# arrayboard_r0.net
KiCad netlist of a schematic drawn in EAGLE
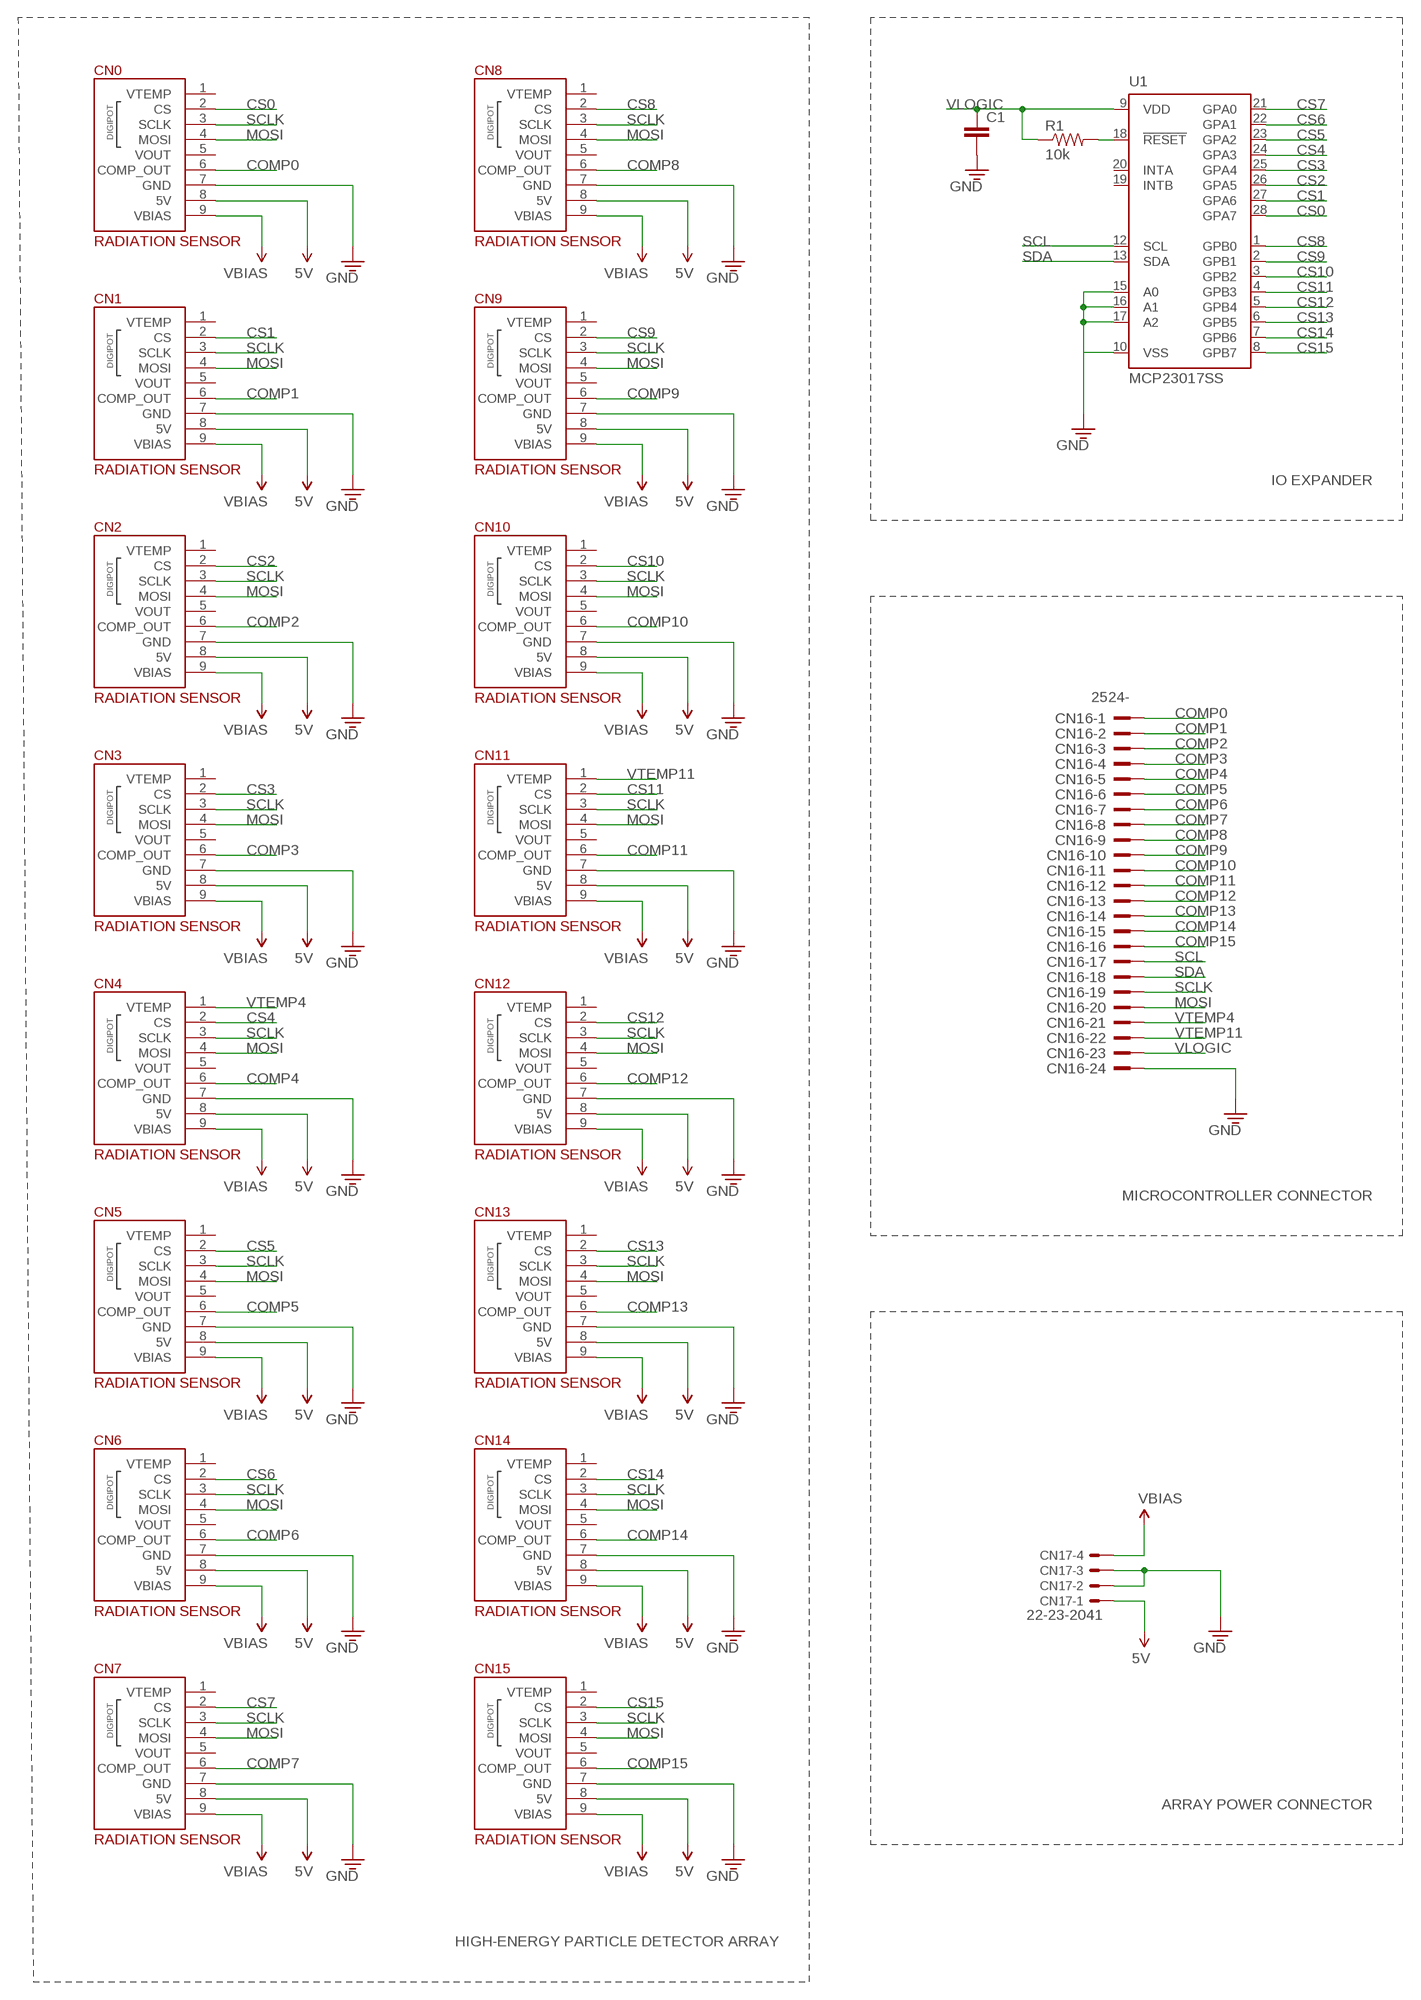
[diagram p0: schematic, sheet 1]

(export (version "E")
  (design (tool "Eeschema 10.0.6"))
  (components
    (comp (ref "C1")
      (value "CAP0603")
      (footprint "eagle-import:0603")
      (libsource (lib "eagle-import") (part "CAP0603"))
    )
    (comp (ref "CN0")
      (value "RADIATION-SENSOR-REV1")
      (footprint "eagle-import:RADIATION-SENSOR-REV1")
      (libsource (lib "eagle-import") (part "RADIATION-SENSOR-REV1"))
    )
    (comp (ref "CN1")
      (value "RADIATION-SENSOR-REV1")
      (footprint "eagle-import:RADIATION-SENSOR-REV1")
      (libsource (lib "eagle-import") (part "RADIATION-SENSOR-REV1"))
    )
    (comp (ref "CN2")
      (value "RADIATION-SENSOR-REV1")
      (footprint "eagle-import:RADIATION-SENSOR-REV1")
      (libsource (lib "eagle-import") (part "RADIATION-SENSOR-REV1"))
    )
    (comp (ref "CN3")
      (value "RADIATION-SENSOR-REV1")
      (footprint "eagle-import:RADIATION-SENSOR-REV1")
      (libsource (lib "eagle-import") (part "RADIATION-SENSOR-REV1"))
    )
    (comp (ref "CN4")
      (value "RADIATION-SENSOR-REV1")
      (footprint "eagle-import:RADIATION-SENSOR-REV1")
      (libsource (lib "eagle-import") (part "RADIATION-SENSOR-REV1"))
    )
    (comp (ref "CN5")
      (value "RADIATION-SENSOR-REV1")
      (footprint "eagle-import:RADIATION-SENSOR-REV1")
      (libsource (lib "eagle-import") (part "RADIATION-SENSOR-REV1"))
    )
    (comp (ref "CN6")
      (value "RADIATION-SENSOR-REV1")
      (footprint "eagle-import:RADIATION-SENSOR-REV1")
      (libsource (lib "eagle-import") (part "RADIATION-SENSOR-REV1"))
    )
    (comp (ref "CN7")
      (value "RADIATION-SENSOR-REV1")
      (footprint "eagle-import:RADIATION-SENSOR-REV1")
      (libsource (lib "eagle-import") (part "RADIATION-SENSOR-REV1"))
    )
    (comp (ref "CN8")
      (value "RADIATION-SENSOR-REV1")
      (footprint "eagle-import:RADIATION-SENSOR-REV1")
      (libsource (lib "eagle-import") (part "RADIATION-SENSOR-REV1"))
    )
    (comp (ref "CN9")
      (value "RADIATION-SENSOR-REV1")
      (footprint "eagle-import:RADIATION-SENSOR-REV1")
      (libsource (lib "eagle-import") (part "RADIATION-SENSOR-REV1"))
    )
    (comp (ref "CN10")
      (value "RADIATION-SENSOR-REV1")
      (footprint "eagle-import:RADIATION-SENSOR-REV1")
      (libsource (lib "eagle-import") (part "RADIATION-SENSOR-REV1"))
    )
    (comp (ref "CN11")
      (value "RADIATION-SENSOR-REV1")
      (footprint "eagle-import:RADIATION-SENSOR-REV1")
      (libsource (lib "eagle-import") (part "RADIATION-SENSOR-REV1"))
    )
    (comp (ref "CN12")
      (value "RADIATION-SENSOR-REV1")
      (footprint "eagle-import:RADIATION-SENSOR-REV1")
      (libsource (lib "eagle-import") (part "RADIATION-SENSOR-REV1"))
    )
    (comp (ref "CN13")
      (value "RADIATION-SENSOR-REV1")
      (footprint "eagle-import:RADIATION-SENSOR-REV1")
      (libsource (lib "eagle-import") (part "RADIATION-SENSOR-REV1"))
    )
    (comp (ref "CN14")
      (value "RADIATION-SENSOR-REV1")
      (footprint "eagle-import:RADIATION-SENSOR-REV1")
      (libsource (lib "eagle-import") (part "RADIATION-SENSOR-REV1"))
    )
    (comp (ref "CN15")
      (value "RADIATION-SENSOR-REV1")
      (footprint "eagle-import:RADIATION-SENSOR-REV1")
      (libsource (lib "eagle-import") (part "RADIATION-SENSOR-REV1"))
    )
    (comp (ref "CN16")
      (value "2524-")
      (footprint "eagle-import:PAK100_2500-24")
      (libsource (lib "eagle-import") (part "2524-"))
    )
    (comp (ref "CN17")
      (value "22-23-2041")
      (footprint "eagle-import:22-23-2041")
      (fields (field (name "MF") "MOLEX"))
      (libsource (lib "eagle-import") (part "22-23-2041"))
    )
    (comp (ref "R1")
      (value "10k")
      (footprint "eagle-import:0603")
      (libsource (lib "eagle-import") (part "RESISTOR0603"))
    )
    (comp (ref "U1")
      (value "MCP23017SS")
      (footprint "eagle-import:SSOP28")
      (libsource (lib "eagle-import") (part "MCP23017SS"))
    )
  )
  (nets
    (net (code "1") (name "/COMP0") (class "Default")
      (node (ref "CN0") (pin "6") (pinfunction "COMP_OUT_6") (pintype "bidirectional"))
      (node (ref "CN16") (pin "1") (pinfunction "KL_1") (pintype "passive"))
    )
    (net (code "2") (name "/COMP1") (class "Default")
      (node (ref "CN1") (pin "6") (pinfunction "COMP_OUT_6") (pintype "bidirectional"))
      (node (ref "CN16") (pin "2") (pinfunction "KL_2") (pintype "passive"))
    )
    (net (code "3") (name "/COMP2") (class "Default")
      (node (ref "CN16") (pin "3") (pinfunction "KL_3") (pintype "passive"))
      (node (ref "CN2") (pin "6") (pinfunction "COMP_OUT_6") (pintype "bidirectional"))
    )
    (net (code "4") (name "/COMP3") (class "Default")
      (node (ref "CN16") (pin "4") (pinfunction "KL_4") (pintype "passive"))
      (node (ref "CN3") (pin "6") (pinfunction "COMP_OUT_6") (pintype "bidirectional"))
    )
    (net (code "5") (name "/COMP4") (class "Default")
      (node (ref "CN16") (pin "5") (pinfunction "KL_5") (pintype "passive"))
      (node (ref "CN4") (pin "6") (pinfunction "COMP_OUT_6") (pintype "bidirectional"))
    )
    (net (code "6") (name "/COMP5") (class "Default")
      (node (ref "CN16") (pin "6") (pinfunction "KL_6") (pintype "passive"))
      (node (ref "CN5") (pin "6") (pinfunction "COMP_OUT_6") (pintype "bidirectional"))
    )
    (net (code "7") (name "/COMP6") (class "Default")
      (node (ref "CN16") (pin "7") (pinfunction "KL_7") (pintype "passive"))
      (node (ref "CN6") (pin "6") (pinfunction "COMP_OUT_6") (pintype "bidirectional"))
    )
    (net (code "8") (name "/COMP7") (class "Default")
      (node (ref "CN16") (pin "8") (pinfunction "KL_8") (pintype "passive"))
      (node (ref "CN7") (pin "6") (pinfunction "COMP_OUT_6") (pintype "bidirectional"))
    )
    (net (code "9") (name "/COMP8") (class "Default")
      (node (ref "CN16") (pin "9") (pinfunction "KL_9") (pintype "passive"))
      (node (ref "CN8") (pin "6") (pinfunction "COMP_OUT_6") (pintype "bidirectional"))
    )
    (net (code "10") (name "/COMP9") (class "Default")
      (node (ref "CN16") (pin "10") (pinfunction "KL_10") (pintype "passive"))
      (node (ref "CN9") (pin "6") (pinfunction "COMP_OUT_6") (pintype "bidirectional"))
    )
    (net (code "11") (name "/COMP10") (class "Default")
      (node (ref "CN10") (pin "6") (pinfunction "COMP_OUT_6") (pintype "bidirectional"))
      (node (ref "CN16") (pin "11") (pinfunction "KL_11") (pintype "passive"))
    )
    (net (code "12") (name "/COMP11") (class "Default")
      (node (ref "CN11") (pin "6") (pinfunction "COMP_OUT_6") (pintype "bidirectional"))
      (node (ref "CN16") (pin "12") (pinfunction "KL_12") (pintype "passive"))
    )
    (net (code "13") (name "/COMP12") (class "Default")
      (node (ref "CN12") (pin "6") (pinfunction "COMP_OUT_6") (pintype "bidirectional"))
      (node (ref "CN16") (pin "13") (pinfunction "KL_13") (pintype "passive"))
    )
    (net (code "14") (name "/COMP13") (class "Default")
      (node (ref "CN13") (pin "6") (pinfunction "COMP_OUT_6") (pintype "bidirectional"))
      (node (ref "CN16") (pin "14") (pinfunction "KL_14") (pintype "passive"))
    )
    (net (code "15") (name "/COMP14") (class "Default")
      (node (ref "CN14") (pin "6") (pinfunction "COMP_OUT_6") (pintype "bidirectional"))
      (node (ref "CN16") (pin "15") (pinfunction "KL_15") (pintype "passive"))
    )
    (net (code "16") (name "/COMP15") (class "Default")
      (node (ref "CN15") (pin "6") (pinfunction "COMP_OUT_6") (pintype "bidirectional"))
      (node (ref "CN16") (pin "16") (pinfunction "KL_16") (pintype "passive"))
    )
    (net (code "17") (name "/CS0") (class "Default")
      (node (ref "CN0") (pin "2") (pinfunction "CS_2") (pintype "bidirectional"))
      (node (ref "U1") (pin "28") (pinfunction "GPA7_28") (pintype "bidirectional"))
    )
    (net (code "18") (name "/CS1") (class "Default")
      (node (ref "CN1") (pin "2") (pinfunction "CS_2") (pintype "bidirectional"))
      (node (ref "U1") (pin "27") (pinfunction "GPA6_27") (pintype "bidirectional"))
    )
    (net (code "19") (name "/CS2") (class "Default")
      (node (ref "CN2") (pin "2") (pinfunction "CS_2") (pintype "bidirectional"))
      (node (ref "U1") (pin "26") (pinfunction "GPA5_26") (pintype "bidirectional"))
    )
    (net (code "20") (name "/CS3") (class "Default")
      (node (ref "CN3") (pin "2") (pinfunction "CS_2") (pintype "bidirectional"))
      (node (ref "U1") (pin "25") (pinfunction "GPA4_25") (pintype "bidirectional"))
    )
    (net (code "21") (name "/CS4") (class "Default")
      (node (ref "CN4") (pin "2") (pinfunction "CS_2") (pintype "bidirectional"))
      (node (ref "U1") (pin "24") (pinfunction "GPA3_24") (pintype "bidirectional"))
    )
    (net (code "22") (name "/CS5") (class "Default")
      (node (ref "CN5") (pin "2") (pinfunction "CS_2") (pintype "bidirectional"))
      (node (ref "U1") (pin "23") (pinfunction "GPA2_23") (pintype "bidirectional"))
    )
    (net (code "23") (name "/CS6") (class "Default")
      (node (ref "CN6") (pin "2") (pinfunction "CS_2") (pintype "bidirectional"))
      (node (ref "U1") (pin "22") (pinfunction "GPA1_22") (pintype "bidirectional"))
    )
    (net (code "24") (name "/CS7") (class "Default")
      (node (ref "CN7") (pin "2") (pinfunction "CS_2") (pintype "bidirectional"))
      (node (ref "U1") (pin "21") (pinfunction "GPA0_21") (pintype "bidirectional"))
    )
    (net (code "25") (name "/CS8") (class "Default")
      (node (ref "CN8") (pin "2") (pinfunction "CS_2") (pintype "bidirectional"))
      (node (ref "U1") (pin "1") (pinfunction "GPB0_1") (pintype "bidirectional"))
    )
    (net (code "26") (name "/CS9") (class "Default")
      (node (ref "CN9") (pin "2") (pinfunction "CS_2") (pintype "bidirectional"))
      (node (ref "U1") (pin "2") (pinfunction "GPB1_2") (pintype "bidirectional"))
    )
    (net (code "27") (name "/CS10") (class "Default")
      (node (ref "CN10") (pin "2") (pinfunction "CS_2") (pintype "bidirectional"))
      (node (ref "U1") (pin "3") (pinfunction "GPB2_3") (pintype "bidirectional"))
    )
    (net (code "28") (name "/CS11") (class "Default")
      (node (ref "CN11") (pin "2") (pinfunction "CS_2") (pintype "bidirectional"))
      (node (ref "U1") (pin "4") (pinfunction "GPB3_4") (pintype "bidirectional"))
    )
    (net (code "29") (name "/CS12") (class "Default")
      (node (ref "CN12") (pin "2") (pinfunction "CS_2") (pintype "bidirectional"))
      (node (ref "U1") (pin "5") (pinfunction "GPB4_5") (pintype "bidirectional"))
    )
    (net (code "30") (name "/CS13") (class "Default")
      (node (ref "CN13") (pin "2") (pinfunction "CS_2") (pintype "bidirectional"))
      (node (ref "U1") (pin "6") (pinfunction "GPB5_6") (pintype "bidirectional"))
    )
    (net (code "31") (name "/CS14") (class "Default")
      (node (ref "CN14") (pin "2") (pinfunction "CS_2") (pintype "bidirectional"))
      (node (ref "U1") (pin "7") (pinfunction "GPB6_7") (pintype "bidirectional"))
    )
    (net (code "32") (name "/CS15") (class "Default")
      (node (ref "CN15") (pin "2") (pinfunction "CS_2") (pintype "bidirectional"))
      (node (ref "U1") (pin "8") (pinfunction "GPB7_8") (pintype "bidirectional"))
    )
    (net (code "33") (name "/MOSI") (class "Default")
      (node (ref "CN0") (pin "4") (pinfunction "MOSI_4") (pintype "bidirectional"))
      (node (ref "CN1") (pin "4") (pinfunction "MOSI_4") (pintype "bidirectional"))
      (node (ref "CN10") (pin "4") (pinfunction "MOSI_4") (pintype "bidirectional"))
      (node (ref "CN11") (pin "4") (pinfunction "MOSI_4") (pintype "bidirectional"))
      (node (ref "CN12") (pin "4") (pinfunction "MOSI_4") (pintype "bidirectional"))
      (node (ref "CN13") (pin "4") (pinfunction "MOSI_4") (pintype "bidirectional"))
      (node (ref "CN14") (pin "4") (pinfunction "MOSI_4") (pintype "bidirectional"))
      (node (ref "CN15") (pin "4") (pinfunction "MOSI_4") (pintype "bidirectional"))
      (node (ref "CN16") (pin "20") (pinfunction "KL_20") (pintype "passive"))
      (node (ref "CN2") (pin "4") (pinfunction "MOSI_4") (pintype "bidirectional"))
      (node (ref "CN3") (pin "4") (pinfunction "MOSI_4") (pintype "bidirectional"))
      (node (ref "CN4") (pin "4") (pinfunction "MOSI_4") (pintype "bidirectional"))
      (node (ref "CN5") (pin "4") (pinfunction "MOSI_4") (pintype "bidirectional"))
      (node (ref "CN6") (pin "4") (pinfunction "MOSI_4") (pintype "bidirectional"))
      (node (ref "CN7") (pin "4") (pinfunction "MOSI_4") (pintype "bidirectional"))
      (node (ref "CN8") (pin "4") (pinfunction "MOSI_4") (pintype "bidirectional"))
      (node (ref "CN9") (pin "4") (pinfunction "MOSI_4") (pintype "bidirectional"))
    )
    (net (code "34") (name "/SCL") (class "Default")
      (node (ref "CN16") (pin "17") (pinfunction "KL_17") (pintype "passive"))
      (node (ref "U1") (pin "12") (pinfunction "SCL_12") (pintype "input"))
    )
    (net (code "35") (name "/SCLK") (class "Default")
      (node (ref "CN0") (pin "3") (pinfunction "SCLK_3") (pintype "bidirectional"))
      (node (ref "CN1") (pin "3") (pinfunction "SCLK_3") (pintype "bidirectional"))
      (node (ref "CN10") (pin "3") (pinfunction "SCLK_3") (pintype "bidirectional"))
      (node (ref "CN11") (pin "3") (pinfunction "SCLK_3") (pintype "bidirectional"))
      (node (ref "CN12") (pin "3") (pinfunction "SCLK_3") (pintype "bidirectional"))
      (node (ref "CN13") (pin "3") (pinfunction "SCLK_3") (pintype "bidirectional"))
      (node (ref "CN14") (pin "3") (pinfunction "SCLK_3") (pintype "bidirectional"))
      (node (ref "CN15") (pin "3") (pinfunction "SCLK_3") (pintype "bidirectional"))
      (node (ref "CN16") (pin "19") (pinfunction "KL_19") (pintype "passive"))
      (node (ref "CN2") (pin "3") (pinfunction "SCLK_3") (pintype "bidirectional"))
      (node (ref "CN3") (pin "3") (pinfunction "SCLK_3") (pintype "bidirectional"))
      (node (ref "CN4") (pin "3") (pinfunction "SCLK_3") (pintype "bidirectional"))
      (node (ref "CN5") (pin "3") (pinfunction "SCLK_3") (pintype "bidirectional"))
      (node (ref "CN6") (pin "3") (pinfunction "SCLK_3") (pintype "bidirectional"))
      (node (ref "CN7") (pin "3") (pinfunction "SCLK_3") (pintype "bidirectional"))
      (node (ref "CN8") (pin "3") (pinfunction "SCLK_3") (pintype "bidirectional"))
      (node (ref "CN9") (pin "3") (pinfunction "SCLK_3") (pintype "bidirectional"))
    )
    (net (code "36") (name "/SDA") (class "Default")
      (node (ref "CN16") (pin "18") (pinfunction "KL_18") (pintype "passive"))
      (node (ref "U1") (pin "13") (pinfunction "SDA_13") (pintype "bidirectional"))
    )
    (net (code "37") (name "/VLOGIC") (class "Default")
      (node (ref "C1") (pin "1") (pinfunction "1_1") (pintype "passive"))
      (node (ref "CN16") (pin "23") (pinfunction "KL_23") (pintype "passive"))
      (node (ref "R1") (pin "1") (pinfunction "1_1") (pintype "passive"))
      (node (ref "U1") (pin "9") (pinfunction "VDD_9") (pintype "power_in"))
    )
    (net (code "38") (name "/VTEMP4") (class "Default")
      (node (ref "CN16") (pin "21") (pinfunction "KL_21") (pintype "passive"))
      (node (ref "CN4") (pin "1") (pinfunction "VTEMP_1") (pintype "bidirectional"))
    )
    (net (code "39") (name "/VTEMP11") (class "Default")
      (node (ref "CN11") (pin "1") (pinfunction "VTEMP_1") (pintype "bidirectional"))
      (node (ref "CN16") (pin "22") (pinfunction "KL_22") (pintype "passive"))
    )
    (net (code "40") (name "5V") (class "Default")
      (node (ref "CN0") (pin "8") (pinfunction "5V_8") (pintype "bidirectional"))
      (node (ref "CN1") (pin "8") (pinfunction "5V_8") (pintype "bidirectional"))
      (node (ref "CN10") (pin "8") (pinfunction "5V_8") (pintype "bidirectional"))
      (node (ref "CN11") (pin "8") (pinfunction "5V_8") (pintype "bidirectional"))
      (node (ref "CN12") (pin "8") (pinfunction "5V_8") (pintype "bidirectional"))
      (node (ref "CN13") (pin "8") (pinfunction "5V_8") (pintype "bidirectional"))
      (node (ref "CN14") (pin "8") (pinfunction "5V_8") (pintype "bidirectional"))
      (node (ref "CN15") (pin "8") (pinfunction "5V_8") (pintype "bidirectional"))
      (node (ref "CN17") (pin "1") (pinfunction "S_1") (pintype "passive"))
      (node (ref "CN2") (pin "8") (pinfunction "5V_8") (pintype "bidirectional"))
      (node (ref "CN3") (pin "8") (pinfunction "5V_8") (pintype "bidirectional"))
      (node (ref "CN4") (pin "8") (pinfunction "5V_8") (pintype "bidirectional"))
      (node (ref "CN5") (pin "8") (pinfunction "5V_8") (pintype "bidirectional"))
      (node (ref "CN6") (pin "8") (pinfunction "5V_8") (pintype "bidirectional"))
      (node (ref "CN7") (pin "8") (pinfunction "5V_8") (pintype "bidirectional"))
      (node (ref "CN8") (pin "8") (pinfunction "5V_8") (pintype "bidirectional"))
      (node (ref "CN9") (pin "8") (pinfunction "5V_8") (pintype "bidirectional"))
    )
    (net (code "41") (name "GND") (class "Default")
      (node (ref "C1") (pin "2") (pinfunction "2_2") (pintype "passive"))
      (node (ref "CN0") (pin "7") (pinfunction "GND_7") (pintype "bidirectional"))
      (node (ref "CN1") (pin "7") (pinfunction "GND_7") (pintype "bidirectional"))
      (node (ref "CN10") (pin "7") (pinfunction "GND_7") (pintype "bidirectional"))
      (node (ref "CN11") (pin "7") (pinfunction "GND_7") (pintype "bidirectional"))
      (node (ref "CN12") (pin "7") (pinfunction "GND_7") (pintype "bidirectional"))
      (node (ref "CN13") (pin "7") (pinfunction "GND_7") (pintype "bidirectional"))
      (node (ref "CN14") (pin "7") (pinfunction "GND_7") (pintype "bidirectional"))
      (node (ref "CN15") (pin "7") (pinfunction "GND_7") (pintype "bidirectional"))
      (node (ref "CN16") (pin "24") (pinfunction "KL_24") (pintype "passive"))
      (node (ref "CN17") (pin "2") (pinfunction "S_2") (pintype "passive"))
      (node (ref "CN17") (pin "3") (pinfunction "S_3") (pintype "passive"))
      (node (ref "CN2") (pin "7") (pinfunction "GND_7") (pintype "bidirectional"))
      (node (ref "CN3") (pin "7") (pinfunction "GND_7") (pintype "bidirectional"))
      (node (ref "CN4") (pin "7") (pinfunction "GND_7") (pintype "bidirectional"))
      (node (ref "CN5") (pin "7") (pinfunction "GND_7") (pintype "bidirectional"))
      (node (ref "CN6") (pin "7") (pinfunction "GND_7") (pintype "bidirectional"))
      (node (ref "CN7") (pin "7") (pinfunction "GND_7") (pintype "bidirectional"))
      (node (ref "CN8") (pin "7") (pinfunction "GND_7") (pintype "bidirectional"))
      (node (ref "CN9") (pin "7") (pinfunction "GND_7") (pintype "bidirectional"))
      (node (ref "U1") (pin "10") (pinfunction "VSS_10") (pintype "power_in"))
      (node (ref "U1") (pin "15") (pinfunction "A0_15") (pintype "input"))
      (node (ref "U1") (pin "16") (pinfunction "A1_16") (pintype "input"))
      (node (ref "U1") (pin "17") (pinfunction "A2_17") (pintype "input"))
    )
    (net (code "42") (name "Net-(U1-~{RESET})") (class "Default")
      (node (ref "R1") (pin "2") (pinfunction "2_2") (pintype "passive"))
      (node (ref "U1") (pin "18") (pinfunction "~{RESET}_18") (pintype "input"))
    )
    (net (code "43") (name "VBIAS") (class "Default")
      (node (ref "CN0") (pin "9") (pinfunction "VBIAS_9") (pintype "bidirectional"))
      (node (ref "CN1") (pin "9") (pinfunction "VBIAS_9") (pintype "bidirectional"))
      (node (ref "CN10") (pin "9") (pinfunction "VBIAS_9") (pintype "bidirectional"))
      (node (ref "CN11") (pin "9") (pinfunction "VBIAS_9") (pintype "bidirectional"))
      (node (ref "CN12") (pin "9") (pinfunction "VBIAS_9") (pintype "bidirectional"))
      (node (ref "CN13") (pin "9") (pinfunction "VBIAS_9") (pintype "bidirectional"))
      (node (ref "CN14") (pin "9") (pinfunction "VBIAS_9") (pintype "bidirectional"))
      (node (ref "CN15") (pin "9") (pinfunction "VBIAS_9") (pintype "bidirectional"))
      (node (ref "CN17") (pin "4") (pinfunction "S_4") (pintype "passive"))
      (node (ref "CN2") (pin "9") (pinfunction "VBIAS_9") (pintype "bidirectional"))
      (node (ref "CN3") (pin "9") (pinfunction "VBIAS_9") (pintype "bidirectional"))
      (node (ref "CN4") (pin "9") (pinfunction "VBIAS_9") (pintype "bidirectional"))
      (node (ref "CN5") (pin "9") (pinfunction "VBIAS_9") (pintype "bidirectional"))
      (node (ref "CN6") (pin "9") (pinfunction "VBIAS_9") (pintype "bidirectional"))
      (node (ref "CN7") (pin "9") (pinfunction "VBIAS_9") (pintype "bidirectional"))
      (node (ref "CN8") (pin "9") (pinfunction "VBIAS_9") (pintype "bidirectional"))
      (node (ref "CN9") (pin "9") (pinfunction "VBIAS_9") (pintype "bidirectional"))
    )
    (net (code "44") (name "unconnected-(CN0-VOUT-Pad5)") (class "Default")
      (node (ref "CN0") (pin "5") (pinfunction "VOUT_5") (pintype "bidirectional"))
    )
    (net (code "45") (name "unconnected-(CN0-VTEMP-Pad1)") (class "Default")
      (node (ref "CN0") (pin "1") (pinfunction "VTEMP_1") (pintype "bidirectional"))
    )
    (net (code "46") (name "unconnected-(CN1-VOUT-Pad5)") (class "Default")
      (node (ref "CN1") (pin "5") (pinfunction "VOUT_5") (pintype "bidirectional"))
    )
    (net (code "47") (name "unconnected-(CN1-VTEMP-Pad1)") (class "Default")
      (node (ref "CN1") (pin "1") (pinfunction "VTEMP_1") (pintype "bidirectional"))
    )
    (net (code "48") (name "unconnected-(CN2-VOUT-Pad5)") (class "Default")
      (node (ref "CN2") (pin "5") (pinfunction "VOUT_5") (pintype "bidirectional"))
    )
    (net (code "49") (name "unconnected-(CN2-VTEMP-Pad1)") (class "Default")
      (node (ref "CN2") (pin "1") (pinfunction "VTEMP_1") (pintype "bidirectional"))
    )
    (net (code "50") (name "unconnected-(CN3-VOUT-Pad5)") (class "Default")
      (node (ref "CN3") (pin "5") (pinfunction "VOUT_5") (pintype "bidirectional"))
    )
    (net (code "51") (name "unconnected-(CN3-VTEMP-Pad1)") (class "Default")
      (node (ref "CN3") (pin "1") (pinfunction "VTEMP_1") (pintype "bidirectional"))
    )
    (net (code "52") (name "unconnected-(CN4-VOUT-Pad5)") (class "Default")
      (node (ref "CN4") (pin "5") (pinfunction "VOUT_5") (pintype "bidirectional"))
    )
    (net (code "53") (name "unconnected-(CN5-VOUT-Pad5)") (class "Default")
      (node (ref "CN5") (pin "5") (pinfunction "VOUT_5") (pintype "bidirectional"))
    )
    (net (code "54") (name "unconnected-(CN5-VTEMP-Pad1)") (class "Default")
      (node (ref "CN5") (pin "1") (pinfunction "VTEMP_1") (pintype "bidirectional"))
    )
    (net (code "55") (name "unconnected-(CN6-VOUT-Pad5)") (class "Default")
      (node (ref "CN6") (pin "5") (pinfunction "VOUT_5") (pintype "bidirectional"))
    )
    (net (code "56") (name "unconnected-(CN6-VTEMP-Pad1)") (class "Default")
      (node (ref "CN6") (pin "1") (pinfunction "VTEMP_1") (pintype "bidirectional"))
    )
    (net (code "57") (name "unconnected-(CN7-VOUT-Pad5)") (class "Default")
      (node (ref "CN7") (pin "5") (pinfunction "VOUT_5") (pintype "bidirectional"))
    )
    (net (code "58") (name "unconnected-(CN7-VTEMP-Pad1)") (class "Default")
      (node (ref "CN7") (pin "1") (pinfunction "VTEMP_1") (pintype "bidirectional"))
    )
    (net (code "59") (name "unconnected-(CN8-VOUT-Pad5)") (class "Default")
      (node (ref "CN8") (pin "5") (pinfunction "VOUT_5") (pintype "bidirectional"))
    )
    (net (code "60") (name "unconnected-(CN8-VTEMP-Pad1)") (class "Default")
      (node (ref "CN8") (pin "1") (pinfunction "VTEMP_1") (pintype "bidirectional"))
    )
    (net (code "61") (name "unconnected-(CN9-VOUT-Pad5)") (class "Default")
      (node (ref "CN9") (pin "5") (pinfunction "VOUT_5") (pintype "bidirectional"))
    )
    (net (code "62") (name "unconnected-(CN9-VTEMP-Pad1)") (class "Default")
      (node (ref "CN9") (pin "1") (pinfunction "VTEMP_1") (pintype "bidirectional"))
    )
    (net (code "63") (name "unconnected-(CN10-VOUT-Pad5)") (class "Default")
      (node (ref "CN10") (pin "5") (pinfunction "VOUT_5") (pintype "bidirectional"))
    )
    (net (code "64") (name "unconnected-(CN10-VTEMP-Pad1)") (class "Default")
      (node (ref "CN10") (pin "1") (pinfunction "VTEMP_1") (pintype "bidirectional"))
    )
    (net (code "65") (name "unconnected-(CN11-VOUT-Pad5)") (class "Default")
      (node (ref "CN11") (pin "5") (pinfunction "VOUT_5") (pintype "bidirectional"))
    )
    (net (code "66") (name "unconnected-(CN12-VOUT-Pad5)") (class "Default")
      (node (ref "CN12") (pin "5") (pinfunction "VOUT_5") (pintype "bidirectional"))
    )
    (net (code "67") (name "unconnected-(CN12-VTEMP-Pad1)") (class "Default")
      (node (ref "CN12") (pin "1") (pinfunction "VTEMP_1") (pintype "bidirectional"))
    )
    (net (code "68") (name "unconnected-(CN13-VOUT-Pad5)") (class "Default")
      (node (ref "CN13") (pin "5") (pinfunction "VOUT_5") (pintype "bidirectional"))
    )
    (net (code "69") (name "unconnected-(CN13-VTEMP-Pad1)") (class "Default")
      (node (ref "CN13") (pin "1") (pinfunction "VTEMP_1") (pintype "bidirectional"))
    )
    (net (code "70") (name "unconnected-(CN14-VOUT-Pad5)") (class "Default")
      (node (ref "CN14") (pin "5") (pinfunction "VOUT_5") (pintype "bidirectional"))
    )
    (net (code "71") (name "unconnected-(CN14-VTEMP-Pad1)") (class "Default")
      (node (ref "CN14") (pin "1") (pinfunction "VTEMP_1") (pintype "bidirectional"))
    )
    (net (code "72") (name "unconnected-(CN15-VOUT-Pad5)") (class "Default")
      (node (ref "CN15") (pin "5") (pinfunction "VOUT_5") (pintype "bidirectional"))
    )
    (net (code "73") (name "unconnected-(CN15-VTEMP-Pad1)") (class "Default")
      (node (ref "CN15") (pin "1") (pinfunction "VTEMP_1") (pintype "bidirectional"))
    )
    (net (code "74") (name "unconnected-(U1-INTA-Pad20)") (class "Default")
      (node (ref "U1") (pin "20") (pinfunction "INTA_20") (pintype "output"))
    )
    (net (code "75") (name "unconnected-(U1-INTB-Pad19)") (class "Default")
      (node (ref "U1") (pin "19") (pinfunction "INTB_19") (pintype "output"))
    )
  )
)
